# unity_gain_buffer.net
KiCad netlist of a schematic drawn in Altium Designer
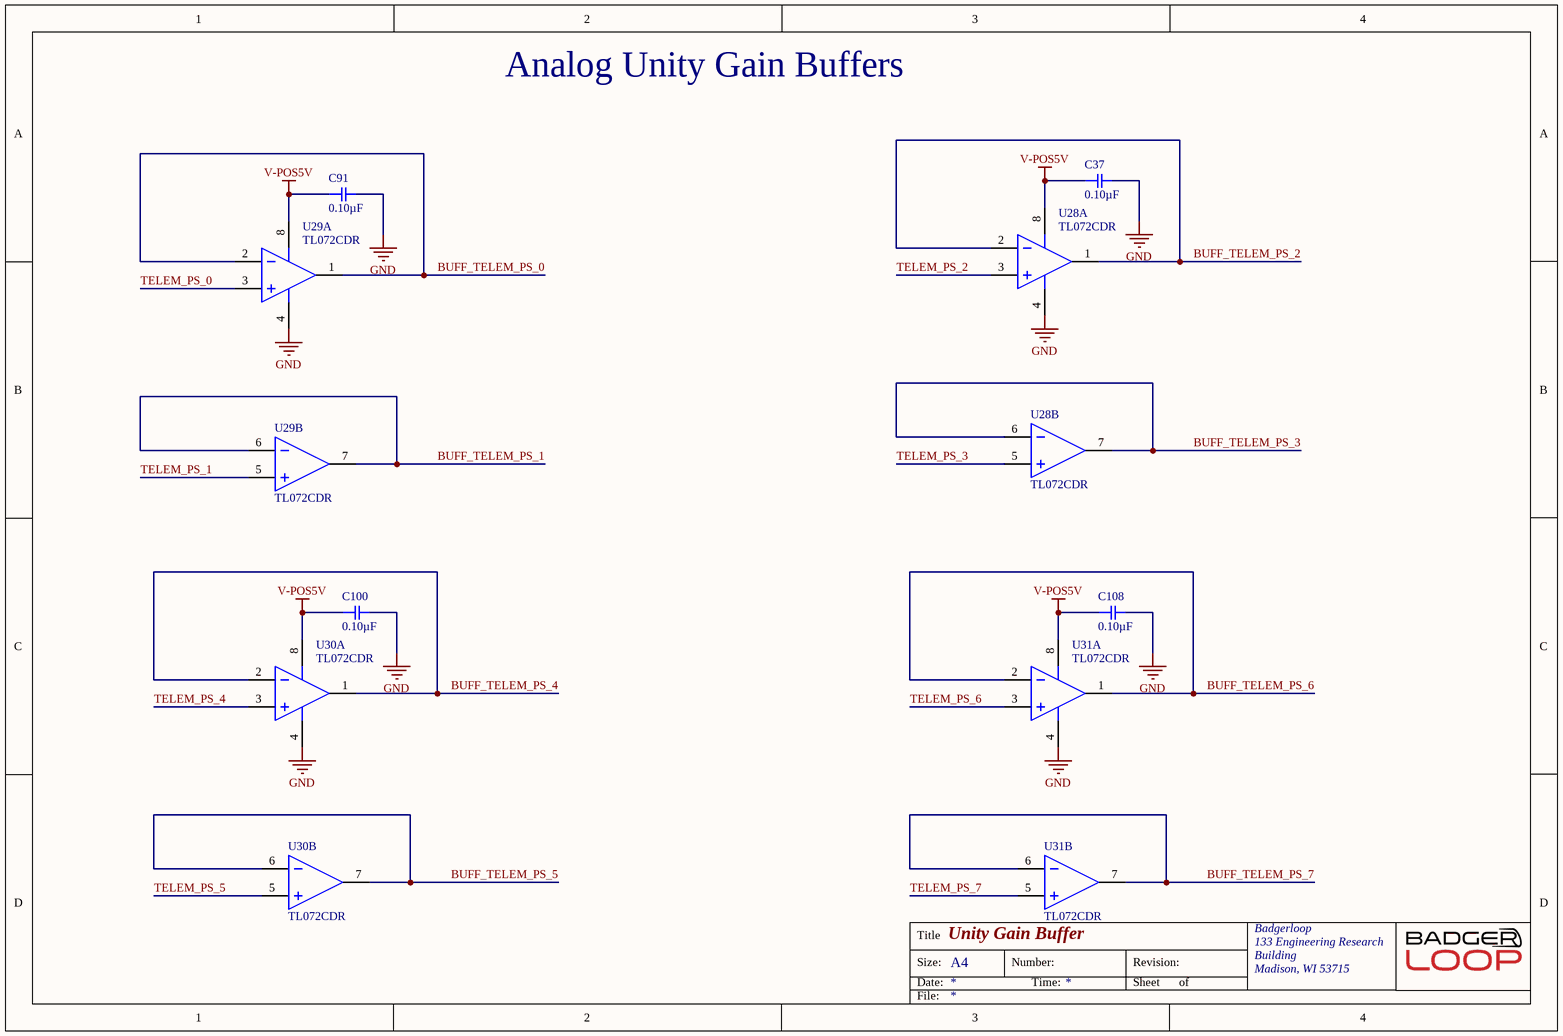
[diagram p0: unity_gain_buffer.SchDoc]

(export (version "E")
  (design (tool "Eeschema 10.0.6"))
  (components
    (comp (ref "C37")
      (value "0.10µF")
      (footprint "SMD-0805C")
      (description "CAP CER 0.1UF 10V U2J 0805")
      (fields
        (field (name "DIGI-KEY PART NUMBER") "490-11592-1-ND")
        (field (name "PART NUMBER") "GRM21B7U1A104JA01L")
      )
      (libsource (lib "capacitors") (part "GRM21B7U1A104JA01L"))
    )
    (comp (ref "C91")
      (value "0.10µF")
      (footprint "SMD-0805C")
      (description "CAP CER 0.1UF 10V U2J 0805")
      (fields
        (field (name "DIGI-KEY PART NUMBER") "490-11592-1-ND")
        (field (name "PART NUMBER") "GRM21B7U1A104JA01L")
      )
      (libsource (lib "capacitors") (part "GRM21B7U1A104JA01L"))
    )
    (comp (ref "C100")
      (value "0.10µF")
      (footprint "SMD-0805C")
      (description "CAP CER 0.1UF 10V U2J 0805")
      (fields
        (field (name "DIGI-KEY PART NUMBER") "490-11592-1-ND")
        (field (name "PART NUMBER") "GRM21B7U1A104JA01L")
      )
      (libsource (lib "capacitors") (part "GRM21B7U1A104JA01L"))
    )
    (comp (ref "C108")
      (value "0.10µF")
      (footprint "SMD-0805C")
      (description "CAP CER 0.1UF 10V U2J 0805")
      (fields
        (field (name "DIGI-KEY PART NUMBER") "490-11592-1-ND")
        (field (name "PART NUMBER") "GRM21B7U1A104JA01L")
      )
      (libsource (lib "capacitors") (part "GRM21B7U1A104JA01L"))
    )
    (comp (ref "U28")
      (value "TL072CDR")
      (footprint "SOP127P600X175-8N")
      (description "IC OPAMP JFET 3MHZ 8SOIC")
      (fields (field (name "MANUFACTURER") "Texas Instruments"))
      (libsource (lib "ic") (part "TL072CDR"))
    )
    (comp (ref "U29")
      (value "TL072CDR")
      (footprint "SOP127P600X175-8N")
      (description "IC OPAMP JFET 3MHZ 8SOIC")
      (fields (field (name "MANUFACTURER") "Texas Instruments"))
      (libsource (lib "ic") (part "TL072CDR"))
    )
    (comp (ref "U30")
      (value "TL072CDR")
      (footprint "SOP127P600X175-8N")
      (description "IC OPAMP JFET 3MHZ 8SOIC")
      (fields (field (name "MANUFACTURER") "Texas Instruments"))
      (libsource (lib "ic") (part "TL072CDR"))
    )
    (comp (ref "U31")
      (value "TL072CDR")
      (footprint "SOP127P600X175-8N")
      (description "IC OPAMP JFET 3MHZ 8SOIC")
      (fields (field (name "MANUFACTURER") "Texas Instruments"))
      (libsource (lib "ic") (part "TL072CDR"))
    )
  )
  (nets
    (net (code "1") (name "/BUFF_TELEM_PS_0") (class "Default")
      (node (ref "U29") (pin "1") (pinfunction "OUT_1") (pintype "passive"))
      (node (ref "U29") (pin "2") (pinfunction "IN-_2") (pintype "passive"))
    )
    (net (code "2") (name "/BUFF_TELEM_PS_1") (class "Default")
      (node (ref "U29") (pin "6") (pinfunction "IN-_6") (pintype "passive"))
      (node (ref "U29") (pin "7") (pinfunction "OUT_7") (pintype "passive"))
    )
    (net (code "3") (name "/BUFF_TELEM_PS_2") (class "Default")
      (node (ref "U28") (pin "1") (pinfunction "OUT_1") (pintype "passive"))
      (node (ref "U28") (pin "2") (pinfunction "IN-_2") (pintype "passive"))
    )
    (net (code "4") (name "/BUFF_TELEM_PS_3") (class "Default")
      (node (ref "U28") (pin "6") (pinfunction "IN-_6") (pintype "passive"))
      (node (ref "U28") (pin "7") (pinfunction "OUT_7") (pintype "passive"))
    )
    (net (code "5") (name "/BUFF_TELEM_PS_4") (class "Default")
      (node (ref "U30") (pin "1") (pinfunction "OUT_1") (pintype "passive"))
      (node (ref "U30") (pin "2") (pinfunction "IN-_2") (pintype "passive"))
    )
    (net (code "6") (name "/BUFF_TELEM_PS_5") (class "Default")
      (node (ref "U30") (pin "6") (pinfunction "IN-_6") (pintype "passive"))
      (node (ref "U30") (pin "7") (pinfunction "OUT_7") (pintype "passive"))
    )
    (net (code "7") (name "/BUFF_TELEM_PS_6") (class "Default")
      (node (ref "U31") (pin "1") (pinfunction "OUT_1") (pintype "passive"))
      (node (ref "U31") (pin "2") (pinfunction "IN-_2") (pintype "passive"))
    )
    (net (code "8") (name "/BUFF_TELEM_PS_7") (class "Default")
      (node (ref "U31") (pin "6") (pinfunction "IN-_6") (pintype "passive"))
      (node (ref "U31") (pin "7") (pinfunction "OUT_7") (pintype "passive"))
    )
    (net (code "9") (name "/TELEM_PS_0") (class "Default")
      (node (ref "U29") (pin "3") (pinfunction "IN+_3") (pintype "passive"))
    )
    (net (code "10") (name "/TELEM_PS_1") (class "Default")
      (node (ref "U29") (pin "5") (pinfunction "IN+_5") (pintype "passive"))
    )
    (net (code "11") (name "/TELEM_PS_2") (class "Default")
      (node (ref "U28") (pin "3") (pinfunction "IN+_3") (pintype "passive"))
    )
    (net (code "12") (name "/TELEM_PS_3") (class "Default")
      (node (ref "U28") (pin "5") (pinfunction "IN+_5") (pintype "passive"))
    )
    (net (code "13") (name "/TELEM_PS_4") (class "Default")
      (node (ref "U30") (pin "3") (pinfunction "IN+_3") (pintype "passive"))
    )
    (net (code "14") (name "/TELEM_PS_5") (class "Default")
      (node (ref "U30") (pin "5") (pinfunction "IN+_5") (pintype "passive"))
    )
    (net (code "15") (name "/TELEM_PS_6") (class "Default")
      (node (ref "U31") (pin "3") (pinfunction "IN+_3") (pintype "passive"))
    )
    (net (code "16") (name "/TELEM_PS_7") (class "Default")
      (node (ref "U31") (pin "5") (pinfunction "IN+_5") (pintype "passive"))
    )
    (net (code "17") (name "GND") (class "Default")
      (node (ref "C100") (pin "2") (pinfunction "2_2") (pintype "passive"))
      (node (ref "C108") (pin "2") (pinfunction "2_2") (pintype "passive"))
      (node (ref "C37") (pin "2") (pinfunction "2_2") (pintype "passive"))
      (node (ref "C91") (pin "2") (pinfunction "2_2") (pintype "passive"))
      (node (ref "U28") (pin "4") (pinfunction "V-_4") (pintype "power_in"))
      (node (ref "U29") (pin "4") (pinfunction "V-_4") (pintype "power_in"))
      (node (ref "U30") (pin "4") (pinfunction "V-_4") (pintype "power_in"))
      (node (ref "U31") (pin "4") (pinfunction "V-_4") (pintype "power_in"))
    )
    (net (code "18") (name "V-POS5V") (class "Default")
      (node (ref "C100") (pin "1") (pinfunction "1_1") (pintype "passive"))
      (node (ref "C108") (pin "1") (pinfunction "1_1") (pintype "passive"))
      (node (ref "C37") (pin "1") (pinfunction "1_1") (pintype "passive"))
      (node (ref "C91") (pin "1") (pinfunction "1_1") (pintype "passive"))
      (node (ref "U28") (pin "8") (pinfunction "V+_8") (pintype "power_in"))
      (node (ref "U29") (pin "8") (pinfunction "V+_8") (pintype "power_in"))
      (node (ref "U30") (pin "8") (pinfunction "V+_8") (pintype "power_in"))
      (node (ref "U31") (pin "8") (pinfunction "V+_8") (pintype "power_in"))
    )
  )
)
